# VoltageLevelMeter1.net
KiCad netlist of a schematic drawn in EAGLE
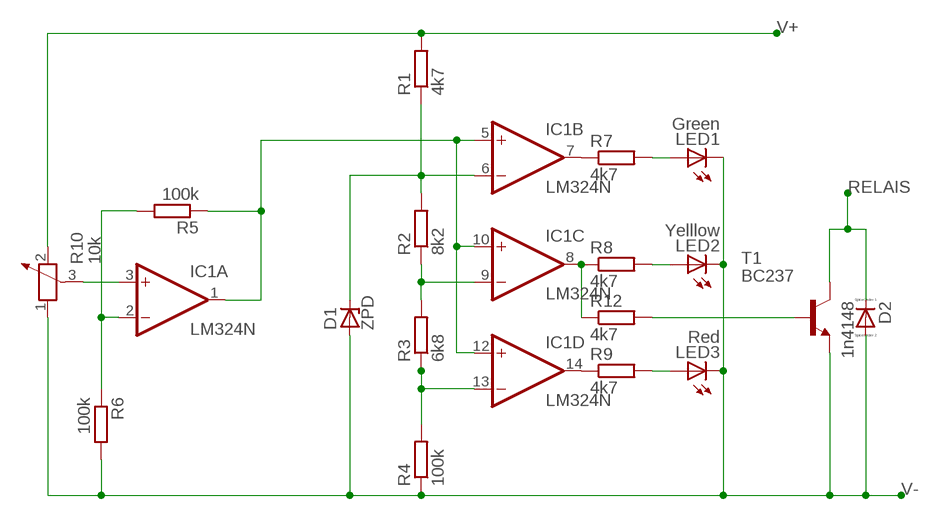
[diagram p0: schematic, sheet 1]

(export (version "E")
  (design (tool "Eeschema 10.0.6"))
  (components
    (comp (ref "D1")
      (value "ZPD")
      (footprint "eagle-import:DO35Z10")
      (libsource (lib "eagle-import") (part "ZPD"))
    )
    (comp (ref "D2")
      (value "1n4148")
      (footprint "eagle-import:DIODE_DO35-7")
      (libsource (lib "eagle-import") (part "DIODE_E-DO35-7"))
    )
    (comp (ref "IC1")
      (value "LM324N")
      (footprint "eagle-import:DIL14")
      (libsource (lib "eagle-import") (part "LM324N"))
    )
    (comp (ref "LED1")
      (value "Green")
      (footprint "eagle-import:LED3MM")
      (libsource (lib "eagle-import") (part "LED3MM"))
    )
    (comp (ref "LED2")
      (value "Yelllow")
      (footprint "eagle-import:LED3MM")
      (libsource (lib "eagle-import") (part "LED3MM"))
    )
    (comp (ref "LED3")
      (value "Red")
      (footprint "eagle-import:LED3MM")
      (libsource (lib "eagle-import") (part "LED3MM"))
    )
    (comp (ref "R1")
      (value "4k7")
      (footprint "eagle-import:0207_7")
      (libsource (lib "eagle-import") (part "R-EU_0207/7"))
    )
    (comp (ref "R2")
      (value "8k2")
      (footprint "eagle-import:0207_7")
      (libsource (lib "eagle-import") (part "R-EU_0207/7"))
    )
    (comp (ref "R3")
      (value "6k8")
      (footprint "eagle-import:0207_7")
      (libsource (lib "eagle-import") (part "R-EU_0207/7"))
    )
    (comp (ref "R4")
      (value "100k")
      (footprint "eagle-import:0207_7")
      (libsource (lib "eagle-import") (part "R-EU_0207/7"))
    )
    (comp (ref "R5")
      (value "100k")
      (footprint "eagle-import:0207_7")
      (libsource (lib "eagle-import") (part "R-EU_0207/7"))
    )
    (comp (ref "R6")
      (value "100k")
      (footprint "eagle-import:0207_7")
      (libsource (lib "eagle-import") (part "R-EU_0207/7"))
    )
    (comp (ref "R7")
      (value "4k7")
      (footprint "eagle-import:0207_7")
      (libsource (lib "eagle-import") (part "R-EU_0207/7"))
    )
    (comp (ref "R8")
      (value "4k7")
      (footprint "eagle-import:0207_7")
      (libsource (lib "eagle-import") (part "R-EU_0207/7"))
    )
    (comp (ref "R9")
      (value "4k7")
      (footprint "eagle-import:0207_7")
      (libsource (lib "eagle-import") (part "R-EU_0207/7"))
    )
    (comp (ref "R10")
      (value "10k")
      (footprint "eagle-import:PT-10")
      (libsource (lib "eagle-import") (part "POTENTIOMETER_PT-10"))
    )
    (comp (ref "R12")
      (value "4k7")
      (footprint "eagle-import:0207_7")
      (libsource (lib "eagle-import") (part "R-EU_0207/7"))
    )
    (comp (ref "T1")
      (value "BC237")
      (footprint "eagle-import:TO92")
      (libsource (lib "eagle-import") (part "BC237"))
    )
  )
  (nets
    (net (code "1") (name "/RELAIS") (class "Default")
      (node (ref "D2") (pin "C") (pinfunction "A_C") (pintype "passive"))
      (node (ref "T1") (pin "3") (pinfunction "C_3") (pintype "passive"))
    )
    (net (code "2") (name "/V+") (class "Default")
      (node (ref "R1") (pin "2") (pinfunction "2_2") (pintype "passive"))
      (node (ref "R10") (pin "2") (pinfunction "2_2") (pintype "passive"))
    )
    (net (code "3") (name "/V-") (class "Default")
      (node (ref "D1") (pin "A") (pinfunction "A_A") (pintype "passive"))
      (node (ref "D2") (pin "A") (pinfunction "C_A") (pintype "passive"))
      (node (ref "LED1") (pin "K") (pinfunction "C_K") (pintype "passive"))
      (node (ref "LED2") (pin "K") (pinfunction "C_K") (pintype "passive"))
      (node (ref "LED3") (pin "K") (pinfunction "C_K") (pintype "passive"))
      (node (ref "R10") (pin "1") (pinfunction "1_1") (pintype "passive"))
      (node (ref "R4") (pin "1") (pinfunction "1_1") (pintype "passive"))
      (node (ref "R6") (pin "2") (pinfunction "2_2") (pintype "passive"))
      (node (ref "T1") (pin "1") (pinfunction "E_1") (pintype "passive"))
    )
    (net (code "4") (name "Net-(IC1A-+IN)") (class "Default")
      (node (ref "IC1") (pin "3") (pinfunction "+IN_3") (pintype "input"))
      (node (ref "R10") (pin "3") (pinfunction "3_3") (pintype "passive"))
    )
    (net (code "5") (name "Net-(IC1A--IN)") (class "Default")
      (node (ref "IC1") (pin "2") (pinfunction "-IN_2") (pintype "input"))
      (node (ref "R5") (pin "2") (pinfunction "2_2") (pintype "passive"))
      (node (ref "R6") (pin "1") (pinfunction "1_1") (pintype "passive"))
    )
    (net (code "6") (name "Net-(IC1A-OUT)") (class "Default")
      (node (ref "IC1") (pin "1") (pinfunction "OUT_1") (pintype "output"))
      (node (ref "IC1") (pin "10") (pinfunction "+IN_10") (pintype "input"))
      (node (ref "IC1") (pin "12") (pinfunction "+IN_12") (pintype "input"))
      (node (ref "IC1") (pin "5") (pinfunction "+IN_5") (pintype "input"))
      (node (ref "R5") (pin "1") (pinfunction "1_1") (pintype "passive"))
    )
    (net (code "7") (name "Net-(IC1B--IN)") (class "Default")
      (node (ref "D1") (pin "C") (pinfunction "C_C") (pintype "passive"))
      (node (ref "IC1") (pin "6") (pinfunction "-IN_6") (pintype "input"))
      (node (ref "R1") (pin "1") (pinfunction "1_1") (pintype "passive"))
      (node (ref "R2") (pin "2") (pinfunction "2_2") (pintype "passive"))
    )
    (net (code "8") (name "Net-(IC1B-OUT)") (class "Default")
      (node (ref "IC1") (pin "7") (pinfunction "OUT_7") (pintype "output"))
      (node (ref "R7") (pin "1") (pinfunction "1_1") (pintype "passive"))
    )
    (net (code "9") (name "Net-(IC1C--IN)") (class "Default")
      (node (ref "IC1") (pin "9") (pinfunction "-IN_9") (pintype "input"))
      (node (ref "R2") (pin "1") (pinfunction "1_1") (pintype "passive"))
      (node (ref "R3") (pin "2") (pinfunction "2_2") (pintype "passive"))
    )
    (net (code "10") (name "Net-(IC1C-OUT)") (class "Default")
      (node (ref "IC1") (pin "8") (pinfunction "OUT_8") (pintype "output"))
      (node (ref "R12") (pin "1") (pinfunction "1_1") (pintype "passive"))
      (node (ref "R8") (pin "1") (pinfunction "1_1") (pintype "passive"))
    )
    (net (code "11") (name "Net-(IC1D--IN)") (class "Default")
      (node (ref "IC1") (pin "13") (pinfunction "-IN_13") (pintype "input"))
      (node (ref "R3") (pin "1") (pinfunction "1_1") (pintype "passive"))
      (node (ref "R4") (pin "2") (pinfunction "2_2") (pintype "passive"))
    )
    (net (code "12") (name "Net-(IC1D-OUT)") (class "Default")
      (node (ref "IC1") (pin "14") (pinfunction "OUT_14") (pintype "output"))
      (node (ref "R9") (pin "1") (pinfunction "1_1") (pintype "passive"))
    )
    (net (code "13") (name "Net-(LED1-PadA)") (class "Default")
      (node (ref "LED1") (pin "A") (pinfunction "A_A") (pintype "passive"))
      (node (ref "R7") (pin "2") (pinfunction "2_2") (pintype "passive"))
    )
    (net (code "14") (name "Net-(LED2-PadA)") (class "Default")
      (node (ref "LED2") (pin "A") (pinfunction "A_A") (pintype "passive"))
      (node (ref "R8") (pin "2") (pinfunction "2_2") (pintype "passive"))
    )
    (net (code "15") (name "Net-(LED3-PadA)") (class "Default")
      (node (ref "LED3") (pin "A") (pinfunction "A_A") (pintype "passive"))
      (node (ref "R9") (pin "2") (pinfunction "2_2") (pintype "passive"))
    )
    (net (code "16") (name "Net-(T1-B)") (class "Default")
      (node (ref "R12") (pin "2") (pinfunction "2_2") (pintype "passive"))
      (node (ref "T1") (pin "2") (pinfunction "B_2") (pintype "passive"))
    )
  )
)
